# TERMINAL_SHIELD_ESP32.net
KiCad netlist of a schematic drawn in EAGLE
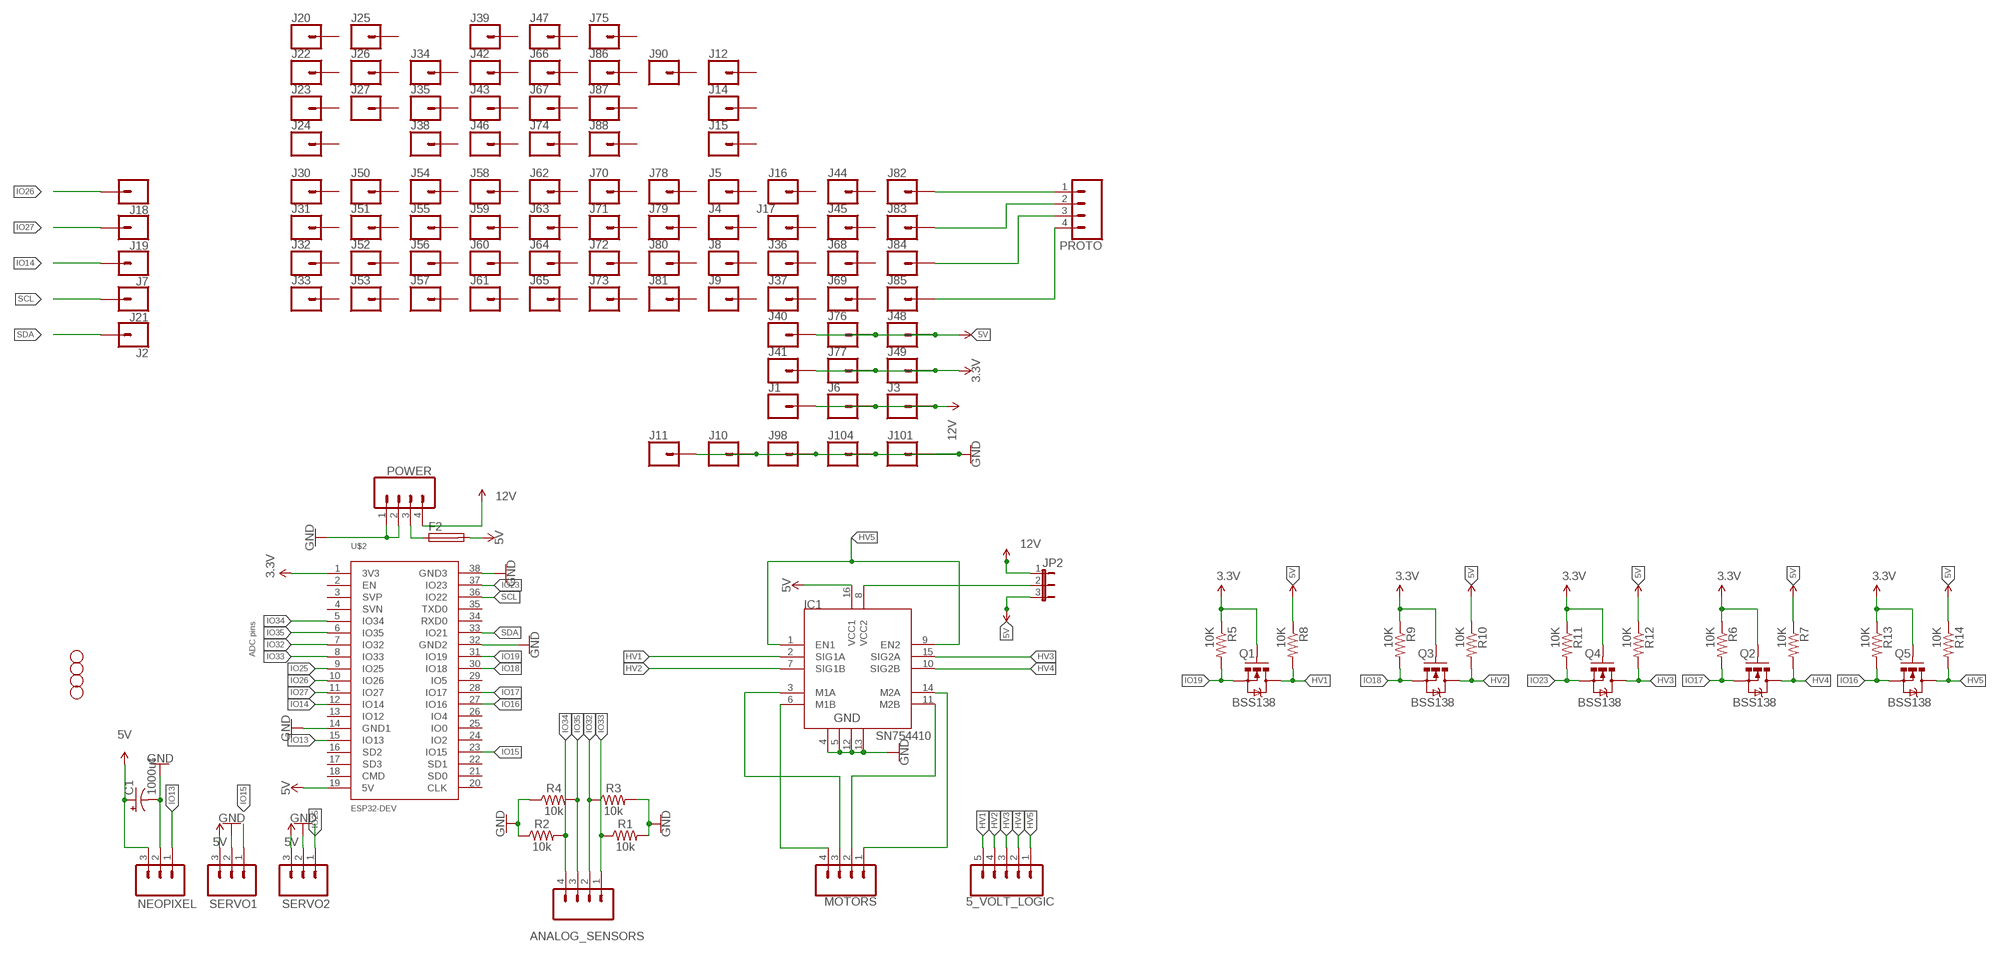
[diagram p0: schematic, sheet 1]

(export (version "E")
  (design (tool "Eeschema 10.0.6"))
  (components
    (comp (ref "5_VOLT_LOGIC")
      (value "CONN_05SCREW")
      (footprint "eagle-import:SCREWTERMINAL-3.5MM-5")
      (libsource (lib "eagle-import") (part "CONN_05SCREW"))
    )
    (comp (ref "ANALOG_SENSORS")
      (value "CONN_04SCREW")
      (footprint "eagle-import:SCREWTERMINAL-3.5MM-4")
      (libsource (lib "eagle-import") (part "CONN_04SCREW"))
    )
    (comp (ref "C1")
      (value "1000uf")
      (footprint "eagle-import:CPOL-RADIAL-5MM-10MM")
      (libsource (lib "eagle-import") (part "1000UF-RADIAL-5MM-25V-20%"))
    )
    (comp (ref "F2")
      (value "KS17")
      (footprint "eagle-import:KS17")
      (libsource (lib "eagle-import") (part "KS17"))
    )
    (comp (ref "H1")
      (value "STAND-OFF")
      (footprint "eagle-import:STAND-OFF")
      (libsource (lib "eagle-import") (part "STAND-OFF"))
    )
    (comp (ref "H2")
      (value "STAND-OFF")
      (footprint "eagle-import:STAND-OFF")
      (libsource (lib "eagle-import") (part "STAND-OFF"))
    )
    (comp (ref "H3")
      (value "STAND-OFF")
      (footprint "eagle-import:STAND-OFF")
      (libsource (lib "eagle-import") (part "STAND-OFF"))
    )
    (comp (ref "H4")
      (value "STAND-OFF")
      (footprint "eagle-import:STAND-OFF")
      (libsource (lib "eagle-import") (part "STAND-OFF"))
    )
    (comp (ref "IC1")
      (value "SN754410")
      (footprint "eagle-import:DIP16")
      (fields (field (name "MF") "Texas Instruments"))
      (libsource (lib "eagle-import") (part "SN754410"))
    )
    (comp (ref "J1")
      (value "CONN_01")
      (footprint "eagle-import:1X01")
      (libsource (lib "eagle-import") (part "CONN_01"))
    )
    (comp (ref "J2")
      (value "CONN_01")
      (footprint "eagle-import:1X01")
      (libsource (lib "eagle-import") (part "CONN_01"))
    )
    (comp (ref "J3")
      (value "CONN_01")
      (footprint "eagle-import:1X01")
      (libsource (lib "eagle-import") (part "CONN_01"))
    )
    (comp (ref "J4")
      (value "CONN_01")
      (footprint "eagle-import:1X01")
      (libsource (lib "eagle-import") (part "CONN_01"))
    )
    (comp (ref "J5")
      (value "CONN_01")
      (footprint "eagle-import:1X01")
      (libsource (lib "eagle-import") (part "CONN_01"))
    )
    (comp (ref "J6")
      (value "CONN_01")
      (footprint "eagle-import:1X01")
      (libsource (lib "eagle-import") (part "CONN_01"))
    )
    (comp (ref "J7")
      (value "CONN_01")
      (footprint "eagle-import:1X01")
      (libsource (lib "eagle-import") (part "CONN_01"))
    )
    (comp (ref "J8")
      (value "CONN_01")
      (footprint "eagle-import:1X01")
      (libsource (lib "eagle-import") (part "CONN_01"))
    )
    (comp (ref "J9")
      (value "CONN_01")
      (footprint "eagle-import:1X01")
      (libsource (lib "eagle-import") (part "CONN_01"))
    )
    (comp (ref "J10")
      (value "CONN_01")
      (footprint "eagle-import:1X01")
      (libsource (lib "eagle-import") (part "CONN_01"))
    )
    (comp (ref "J11")
      (value "CONN_01")
      (footprint "eagle-import:1X01")
      (libsource (lib "eagle-import") (part "CONN_01"))
    )
    (comp (ref "J12")
      (value "CONN_01")
      (footprint "eagle-import:1X01")
      (libsource (lib "eagle-import") (part "CONN_01"))
    )
    (comp (ref "J14")
      (value "CONN_01")
      (footprint "eagle-import:1X01")
      (libsource (lib "eagle-import") (part "CONN_01"))
    )
    (comp (ref "J15")
      (value "CONN_01")
      (footprint "eagle-import:1X01")
      (libsource (lib "eagle-import") (part "CONN_01"))
    )
    (comp (ref "J16")
      (value "CONN_01")
      (footprint "eagle-import:1X01")
      (libsource (lib "eagle-import") (part "CONN_01"))
    )
    (comp (ref "J17")
      (value "CONN_01")
      (footprint "eagle-import:1X01")
      (libsource (lib "eagle-import") (part "CONN_01"))
    )
    (comp (ref "J18")
      (value "CONN_01")
      (footprint "eagle-import:1X01")
      (libsource (lib "eagle-import") (part "CONN_01"))
    )
    (comp (ref "J19")
      (value "CONN_01")
      (footprint "eagle-import:1X01")
      (libsource (lib "eagle-import") (part "CONN_01"))
    )
    (comp (ref "J20")
      (value "CONN_01")
      (footprint "eagle-import:1X01")
      (libsource (lib "eagle-import") (part "CONN_01"))
    )
    (comp (ref "J21")
      (value "CONN_01")
      (footprint "eagle-import:1X01")
      (libsource (lib "eagle-import") (part "CONN_01"))
    )
    (comp (ref "J22")
      (value "CONN_01")
      (footprint "eagle-import:1X01")
      (libsource (lib "eagle-import") (part "CONN_01"))
    )
    (comp (ref "J23")
      (value "CONN_01")
      (footprint "eagle-import:1X01")
      (libsource (lib "eagle-import") (part "CONN_01"))
    )
    (comp (ref "J24")
      (value "CONN_01")
      (footprint "eagle-import:1X01")
      (libsource (lib "eagle-import") (part "CONN_01"))
    )
    (comp (ref "J25")
      (value "CONN_01")
      (footprint "eagle-import:1X01")
      (libsource (lib "eagle-import") (part "CONN_01"))
    )
    (comp (ref "J26")
      (value "CONN_01")
      (footprint "eagle-import:1X01")
      (libsource (lib "eagle-import") (part "CONN_01"))
    )
    (comp (ref "J27")
      (value "CONN_01")
      (footprint "eagle-import:1X01")
      (libsource (lib "eagle-import") (part "CONN_01"))
    )
    (comp (ref "J30")
      (value "CONN_01")
      (footprint "eagle-import:1X01")
      (libsource (lib "eagle-import") (part "CONN_01"))
    )
    (comp (ref "J31")
      (value "CONN_01")
      (footprint "eagle-import:1X01")
      (libsource (lib "eagle-import") (part "CONN_01"))
    )
    (comp (ref "J32")
      (value "CONN_01")
      (footprint "eagle-import:1X01")
      (libsource (lib "eagle-import") (part "CONN_01"))
    )
    (comp (ref "J33")
      (value "CONN_01")
      (footprint "eagle-import:1X01")
      (libsource (lib "eagle-import") (part "CONN_01"))
    )
    (comp (ref "J34")
      (value "CONN_01")
      (footprint "eagle-import:1X01")
      (libsource (lib "eagle-import") (part "CONN_01"))
    )
    (comp (ref "J35")
      (value "CONN_01")
      (footprint "eagle-import:1X01")
      (libsource (lib "eagle-import") (part "CONN_01"))
    )
    (comp (ref "J36")
      (value "CONN_01")
      (footprint "eagle-import:1X01")
      (libsource (lib "eagle-import") (part "CONN_01"))
    )
    (comp (ref "J37")
      (value "CONN_01")
      (footprint "eagle-import:1X01")
      (libsource (lib "eagle-import") (part "CONN_01"))
    )
    (comp (ref "J38")
      (value "CONN_01")
      (footprint "eagle-import:1X01")
      (libsource (lib "eagle-import") (part "CONN_01"))
    )
    (comp (ref "J39")
      (value "CONN_01")
      (footprint "eagle-import:1X01")
      (libsource (lib "eagle-import") (part "CONN_01"))
    )
    (comp (ref "J40")
      (value "CONN_01")
      (footprint "eagle-import:1X01")
      (libsource (lib "eagle-import") (part "CONN_01"))
    )
    (comp (ref "J41")
      (value "CONN_01")
      (footprint "eagle-import:1X01")
      (libsource (lib "eagle-import") (part "CONN_01"))
    )
    (comp (ref "J42")
      (value "CONN_01")
      (footprint "eagle-import:1X01")
      (libsource (lib "eagle-import") (part "CONN_01"))
    )
    (comp (ref "J43")
      (value "CONN_01")
      (footprint "eagle-import:1X01")
      (libsource (lib "eagle-import") (part "CONN_01"))
    )
    (comp (ref "J44")
      (value "CONN_01")
      (footprint "eagle-import:1X01")
      (libsource (lib "eagle-import") (part "CONN_01"))
    )
    (comp (ref "J45")
      (value "CONN_01")
      (footprint "eagle-import:1X01")
      (libsource (lib "eagle-import") (part "CONN_01"))
    )
    (comp (ref "J46")
      (value "CONN_01")
      (footprint "eagle-import:1X01")
      (libsource (lib "eagle-import") (part "CONN_01"))
    )
    (comp (ref "J47")
      (value "CONN_01")
      (footprint "eagle-import:1X01")
      (libsource (lib "eagle-import") (part "CONN_01"))
    )
    (comp (ref "J48")
      (value "CONN_01")
      (footprint "eagle-import:1X01")
      (libsource (lib "eagle-import") (part "CONN_01"))
    )
    (comp (ref "J49")
      (value "CONN_01")
      (footprint "eagle-import:1X01")
      (libsource (lib "eagle-import") (part "CONN_01"))
    )
    (comp (ref "J50")
      (value "CONN_01")
      (footprint "eagle-import:1X01")
      (libsource (lib "eagle-import") (part "CONN_01"))
    )
    (comp (ref "J51")
      (value "CONN_01")
      (footprint "eagle-import:1X01")
      (libsource (lib "eagle-import") (part "CONN_01"))
    )
    (comp (ref "J52")
      (value "CONN_01")
      (footprint "eagle-import:1X01")
      (libsource (lib "eagle-import") (part "CONN_01"))
    )
    (comp (ref "J53")
      (value "CONN_01")
      (footprint "eagle-import:1X01")
      (libsource (lib "eagle-import") (part "CONN_01"))
    )
    (comp (ref "J54")
      (value "CONN_01")
      (footprint "eagle-import:1X01")
      (libsource (lib "eagle-import") (part "CONN_01"))
    )
    (comp (ref "J55")
      (value "CONN_01")
      (footprint "eagle-import:1X01")
      (libsource (lib "eagle-import") (part "CONN_01"))
    )
    (comp (ref "J56")
      (value "CONN_01")
      (footprint "eagle-import:1X01")
      (libsource (lib "eagle-import") (part "CONN_01"))
    )
    (comp (ref "J57")
      (value "CONN_01")
      (footprint "eagle-import:1X01")
      (libsource (lib "eagle-import") (part "CONN_01"))
    )
    (comp (ref "J58")
      (value "CONN_01")
      (footprint "eagle-import:1X01")
      (libsource (lib "eagle-import") (part "CONN_01"))
    )
    (comp (ref "J59")
      (value "CONN_01")
      (footprint "eagle-import:1X01")
      (libsource (lib "eagle-import") (part "CONN_01"))
    )
    (comp (ref "J60")
      (value "CONN_01")
      (footprint "eagle-import:1X01")
      (libsource (lib "eagle-import") (part "CONN_01"))
    )
    (comp (ref "J61")
      (value "CONN_01")
      (footprint "eagle-import:1X01")
      (libsource (lib "eagle-import") (part "CONN_01"))
    )
    (comp (ref "J62")
      (value "CONN_01")
      (footprint "eagle-import:1X01")
      (libsource (lib "eagle-import") (part "CONN_01"))
    )
    (comp (ref "J63")
      (value "CONN_01")
      (footprint "eagle-import:1X01")
      (libsource (lib "eagle-import") (part "CONN_01"))
    )
    (comp (ref "J64")
      (value "CONN_01")
      (footprint "eagle-import:1X01")
      (libsource (lib "eagle-import") (part "CONN_01"))
    )
    (comp (ref "J65")
      (value "CONN_01")
      (footprint "eagle-import:1X01")
      (libsource (lib "eagle-import") (part "CONN_01"))
    )
    (comp (ref "J66")
      (value "CONN_01")
      (footprint "eagle-import:1X01")
      (libsource (lib "eagle-import") (part "CONN_01"))
    )
    (comp (ref "J67")
      (value "CONN_01")
      (footprint "eagle-import:1X01")
      (libsource (lib "eagle-import") (part "CONN_01"))
    )
    (comp (ref "J68")
      (value "CONN_01")
      (footprint "eagle-import:1X01")
      (libsource (lib "eagle-import") (part "CONN_01"))
    )
    (comp (ref "J69")
      (value "CONN_01")
      (footprint "eagle-import:1X01")
      (libsource (lib "eagle-import") (part "CONN_01"))
    )
    (comp (ref "J70")
      (value "CONN_01")
      (footprint "eagle-import:1X01")
      (libsource (lib "eagle-import") (part "CONN_01"))
    )
    (comp (ref "J71")
      (value "CONN_01")
      (footprint "eagle-import:1X01")
      (libsource (lib "eagle-import") (part "CONN_01"))
    )
    (comp (ref "J72")
      (value "CONN_01")
      (footprint "eagle-import:1X01")
      (libsource (lib "eagle-import") (part "CONN_01"))
    )
    (comp (ref "J73")
      (value "CONN_01")
      (footprint "eagle-import:1X01")
      (libsource (lib "eagle-import") (part "CONN_01"))
    )
    (comp (ref "J74")
      (value "CONN_01")
      (footprint "eagle-import:1X01")
      (libsource (lib "eagle-import") (part "CONN_01"))
    )
    (comp (ref "J75")
      (value "CONN_01")
      (footprint "eagle-import:1X01")
      (libsource (lib "eagle-import") (part "CONN_01"))
    )
    (comp (ref "J76")
      (value "CONN_01")
      (footprint "eagle-import:1X01")
      (libsource (lib "eagle-import") (part "CONN_01"))
    )
    (comp (ref "J77")
      (value "CONN_01")
      (footprint "eagle-import:1X01")
      (libsource (lib "eagle-import") (part "CONN_01"))
    )
    (comp (ref "J78")
      (value "CONN_01")
      (footprint "eagle-import:1X01")
      (libsource (lib "eagle-import") (part "CONN_01"))
    )
    (comp (ref "J79")
      (value "CONN_01")
      (footprint "eagle-import:1X01")
      (libsource (lib "eagle-import") (part "CONN_01"))
    )
    (comp (ref "J80")
      (value "CONN_01")
      (footprint "eagle-import:1X01")
      (libsource (lib "eagle-import") (part "CONN_01"))
    )
    (comp (ref "J81")
      (value "CONN_01")
      (footprint "eagle-import:1X01")
      (libsource (lib "eagle-import") (part "CONN_01"))
    )
    (comp (ref "J82")
      (value "CONN_01")
      (footprint "eagle-import:1X01")
      (libsource (lib "eagle-import") (part "CONN_01"))
    )
    (comp (ref "J83")
      (value "CONN_01")
      (footprint "eagle-import:1X01")
      (libsource (lib "eagle-import") (part "CONN_01"))
    )
    (comp (ref "J84")
      (value "CONN_01")
      (footprint "eagle-import:1X01")
      (libsource (lib "eagle-import") (part "CONN_01"))
    )
    (comp (ref "J85")
      (value "CONN_01")
      (footprint "eagle-import:1X01")
      (libsource (lib "eagle-import") (part "CONN_01"))
    )
    (comp (ref "J86")
      (value "CONN_01")
      (footprint "eagle-import:1X01")
      (libsource (lib "eagle-import") (part "CONN_01"))
    )
    (comp (ref "J87")
      (value "CONN_01")
      (footprint "eagle-import:1X01")
      (libsource (lib "eagle-import") (part "CONN_01"))
    )
    (comp (ref "J88")
      (value "CONN_01")
      (footprint "eagle-import:1X01")
      (libsource (lib "eagle-import") (part "CONN_01"))
    )
    (comp (ref "J90")
      (value "CONN_01")
      (footprint "eagle-import:1X01")
      (libsource (lib "eagle-import") (part "CONN_01"))
    )
    (comp (ref "J98")
      (value "CONN_01")
      (footprint "eagle-import:1X01")
      (libsource (lib "eagle-import") (part "CONN_01"))
    )
    (comp (ref "J101")
      (value "CONN_01")
      (footprint "eagle-import:1X01")
      (libsource (lib "eagle-import") (part "CONN_01"))
    )
    (comp (ref "J104")
      (value "CONN_01")
      (footprint "eagle-import:1X01")
      (libsource (lib "eagle-import") (part "CONN_01"))
    )
    (comp (ref "JP2")
      (value "JP2E")
      (footprint "eagle-import:JP2")
      (libsource (lib "eagle-import") (part "JP2E"))
    )
    (comp (ref "MOTORS")
      (value "CONN_04SCREW")
      (footprint "eagle-import:SCREWTERMINAL-3.5MM-4")
      (libsource (lib "eagle-import") (part "CONN_04SCREW"))
    )
    (comp (ref "NEOPIXEL")
      (value "CONN_03SCREW")
      (footprint "eagle-import:SCREWTERMINAL-3.5MM-3")
      (libsource (lib "eagle-import") (part "CONN_03SCREW"))
    )
    (comp (ref "POWER")
      (value "CONN_04SCREW")
      (footprint "eagle-import:SCREWTERMINAL-3.5MM-4")
      (libsource (lib "eagle-import") (part "CONN_04SCREW"))
    )
    (comp (ref "PROTO")
      (value "CONN_04SCREW")
      (footprint "eagle-import:SCREWTERMINAL-3.5MM-4")
      (libsource (lib "eagle-import") (part "CONN_04SCREW"))
    )
    (comp (ref "Q1")
      (value "BSS138")
      (footprint "eagle-import:SOT23-3")
      (libsource (lib "eagle-import") (part "MOSFET-NCHANNELSMD"))
    )
    (comp (ref "Q2")
      (value "BSS138")
      (footprint "eagle-import:SOT23-3")
      (libsource (lib "eagle-import") (part "MOSFET-NCHANNELSMD"))
    )
    (comp (ref "Q3")
      (value "BSS138")
      (footprint "eagle-import:SOT23-3")
      (libsource (lib "eagle-import") (part "MOSFET-NCHANNELSMD"))
    )
    (comp (ref "Q4")
      (value "BSS138")
      (footprint "eagle-import:SOT23-3")
      (libsource (lib "eagle-import") (part "MOSFET-NCHANNELSMD"))
    )
    (comp (ref "Q5")
      (value "BSS138")
      (footprint "eagle-import:SOT23-3")
      (libsource (lib "eagle-import") (part "MOSFET-NCHANNELSMD"))
    )
    (comp (ref "R1")
      (value "10k")
      (footprint "eagle-import:AXIAL-0.3")
      (libsource (lib "eagle-import") (part "10KOHM-HORIZ-1/4W-1%"))
    )
    (comp (ref "R2")
      (value "10k")
      (footprint "eagle-import:AXIAL-0.3")
      (libsource (lib "eagle-import") (part "10KOHM-HORIZ-1/4W-1%"))
    )
    (comp (ref "R3")
      (value "10k")
      (footprint "eagle-import:AXIAL-0.3")
      (libsource (lib "eagle-import") (part "10KOHM-HORIZ-1/4W-1%"))
    )
    (comp (ref "R4")
      (value "10k")
      (footprint "eagle-import:AXIAL-0.3")
      (libsource (lib "eagle-import") (part "10KOHM-HORIZ-1/4W-1%"))
    )
    (comp (ref "R5")
      (value "10K")
      (footprint "eagle-import:0805")
      (libsource (lib "eagle-import") (part "RESISTOR0805-RES"))
    )
    (comp (ref "R6")
      (value "10K")
      (footprint "eagle-import:0805")
      (libsource (lib "eagle-import") (part "RESISTOR0805-RES"))
    )
    (comp (ref "R7")
      (value "10K")
      (footprint "eagle-import:0805")
      (libsource (lib "eagle-import") (part "RESISTOR0805-RES"))
    )
    (comp (ref "R8")
      (value "10K")
      (footprint "eagle-import:0805")
      (libsource (lib "eagle-import") (part "RESISTOR0805-RES"))
    )
    (comp (ref "R9")
      (value "10K")
      (footprint "eagle-import:0805")
      (libsource (lib "eagle-import") (part "RESISTOR0805-RES"))
    )
    (comp (ref "R10")
      (value "10K")
      (footprint "eagle-import:0805")
      (libsource (lib "eagle-import") (part "RESISTOR0805-RES"))
    )
    (comp (ref "R11")
      (value "10K")
      (footprint "eagle-import:0805")
      (libsource (lib "eagle-import") (part "RESISTOR0805-RES"))
    )
    (comp (ref "R12")
      (value "10K")
      (footprint "eagle-import:0805")
      (libsource (lib "eagle-import") (part "RESISTOR0805-RES"))
    )
    (comp (ref "R13")
      (value "10K")
      (footprint "eagle-import:0805")
      (libsource (lib "eagle-import") (part "RESISTOR0805-RES"))
    )
    (comp (ref "R14")
      (value "10K")
      (footprint "eagle-import:0805")
      (libsource (lib "eagle-import") (part "RESISTOR0805-RES"))
    )
    (comp (ref "SERVO1")
      (value "CONN_03SCREW")
      (footprint "eagle-import:SCREWTERMINAL-3.5MM-3")
      (libsource (lib "eagle-import") (part "CONN_03SCREW"))
    )
    (comp (ref "SERVO2")
      (value "CONN_03SCREW")
      (footprint "eagle-import:SCREWTERMINAL-3.5MM-3")
      (libsource (lib "eagle-import") (part "CONN_03SCREW"))
    )
    (comp (ref "U$2")
      (value "ESP32-DEV")
      (footprint "eagle-import:ESP32-DEV")
      (libsource (lib "eagle-import") (part "ESP32-DEV"))
    )
  )
  (nets
    (net (code "1") (name "3.3V") (class "Default")
      (node (ref "J41") (pin "1") (pinfunction "1_1") (pintype "passive"))
      (node (ref "J49") (pin "1") (pinfunction "1_1") (pintype "passive"))
      (node (ref "J77") (pin "1") (pinfunction "1_1") (pintype "passive"))
      (node (ref "Q1") (pin "1") (pinfunction "G_1") (pintype "passive"))
      (node (ref "Q2") (pin "1") (pinfunction "G_1") (pintype "passive"))
      (node (ref "Q3") (pin "1") (pinfunction "G_1") (pintype "passive"))
      (node (ref "Q4") (pin "1") (pinfunction "G_1") (pintype "passive"))
      (node (ref "Q5") (pin "1") (pinfunction "G_1") (pintype "passive"))
      (node (ref "R11") (pin "1") (pinfunction "1_1") (pintype "passive"))
      (node (ref "R13") (pin "1") (pinfunction "1_1") (pintype "passive"))
      (node (ref "R5") (pin "1") (pinfunction "1_1") (pintype "passive"))
      (node (ref "R6") (pin "1") (pinfunction "1_1") (pintype "passive"))
      (node (ref "R9") (pin "1") (pinfunction "1_1") (pintype "passive"))
      (node (ref "U$2") (pin "1") (pinfunction "3V3_1") (pintype "bidirectional"))
    )
    (net (code "2") (name "5V") (class "Default")
      (node (ref "C1") (pin "+") (pinfunction "+_+") (pintype "passive"))
      (node (ref "F2") (pin "2") (pinfunction "2_2") (pintype "passive"))
      (node (ref "IC1") (pin "16") (pinfunction "VCC1_16") (pintype "power_in"))
      (node (ref "J40") (pin "1") (pinfunction "1_1") (pintype "passive"))
      (node (ref "J48") (pin "1") (pinfunction "1_1") (pintype "passive"))
      (node (ref "J76") (pin "1") (pinfunction "1_1") (pintype "passive"))
      (node (ref "JP2") (pin "3") (pinfunction "3_3") (pintype "passive"))
      (node (ref "NEOPIXEL") (pin "3") (pinfunction "3_3") (pintype "passive"))
      (node (ref "R10") (pin "1") (pinfunction "1_1") (pintype "passive"))
      (node (ref "R12") (pin "1") (pinfunction "1_1") (pintype "passive"))
      (node (ref "R14") (pin "1") (pinfunction "1_1") (pintype "passive"))
      (node (ref "R7") (pin "1") (pinfunction "1_1") (pintype "passive"))
      (node (ref "R8") (pin "1") (pinfunction "1_1") (pintype "passive"))
      (node (ref "SERVO1") (pin "3") (pinfunction "3_3") (pintype "passive"))
      (node (ref "SERVO2") (pin "3") (pinfunction "3_3") (pintype "passive"))
      (node (ref "U$2") (pin "19") (pinfunction "5V_19") (pintype "bidirectional"))
    )
    (net (code "3") (name "12V") (class "Default")
      (node (ref "J1") (pin "1") (pinfunction "1_1") (pintype "passive"))
      (node (ref "J3") (pin "1") (pinfunction "1_1") (pintype "passive"))
      (node (ref "J6") (pin "1") (pinfunction "1_1") (pintype "passive"))
      (node (ref "JP2") (pin "1") (pinfunction "1_1") (pintype "passive"))
      (node (ref "POWER") (pin "4") (pinfunction "4_4") (pintype "passive"))
    )
    (net (code "4") (name "GND") (class "Default")
      (node (ref "C1") (pin "-") (pinfunction "-_-") (pintype "passive"))
      (node (ref "IC1") (pin "12") (pinfunction "P12_12") (pintype "power_in"))
      (node (ref "IC1") (pin "13") (pinfunction "P13_13") (pintype "power_in"))
      (node (ref "IC1") (pin "4") (pinfunction "P4_4") (pintype "power_in"))
      (node (ref "IC1") (pin "5") (pinfunction "P5_5") (pintype "power_in"))
      (node (ref "J10") (pin "1") (pinfunction "1_1") (pintype "passive"))
      (node (ref "J101") (pin "1") (pinfunction "1_1") (pintype "passive"))
      (node (ref "J104") (pin "1") (pinfunction "1_1") (pintype "passive"))
      (node (ref "J11") (pin "1") (pinfunction "1_1") (pintype "passive"))
      (node (ref "J98") (pin "1") (pinfunction "1_1") (pintype "passive"))
      (node (ref "NEOPIXEL") (pin "2") (pinfunction "2_2") (pintype "passive"))
      (node (ref "POWER") (pin "1") (pinfunction "1_1") (pintype "passive"))
      (node (ref "POWER") (pin "2") (pinfunction "2_2") (pintype "passive"))
      (node (ref "R1") (pin "P$2") (pinfunction "2_P$2") (pintype "passive"))
      (node (ref "R2") (pin "P$1") (pinfunction "1_P$1") (pintype "passive"))
      (node (ref "R3") (pin "P$2") (pinfunction "2_P$2") (pintype "passive"))
      (node (ref "R4") (pin "P$1") (pinfunction "1_P$1") (pintype "passive"))
      (node (ref "SERVO1") (pin "2") (pinfunction "2_2") (pintype "passive"))
      (node (ref "SERVO2") (pin "2") (pinfunction "2_2") (pintype "passive"))
      (node (ref "U$2") (pin "14") (pinfunction "GND1_14") (pintype "bidirectional"))
      (node (ref "U$2") (pin "32") (pinfunction "GND2_32") (pintype "bidirectional"))
      (node (ref "U$2") (pin "38") (pinfunction "GND3_38") (pintype "bidirectional"))
    )
    (net (code "5") (name "HV1") (class "Default")
      (node (ref "5_VOLT_LOGIC") (pin "5") (pinfunction "5_5") (pintype "passive"))
      (node (ref "IC1") (pin "2") (pinfunction "SIG1A_2") (pintype "bidirectional"))
      (node (ref "Q1") (pin "3") (pinfunction "D_3") (pintype "passive"))
      (node (ref "R8") (pin "2") (pinfunction "2_2") (pintype "passive"))
    )
    (net (code "6") (name "HV2") (class "Default")
      (node (ref "5_VOLT_LOGIC") (pin "4") (pinfunction "4_4") (pintype "passive"))
      (node (ref "IC1") (pin "7") (pinfunction "SIG1B_7") (pintype "bidirectional"))
      (node (ref "Q3") (pin "3") (pinfunction "D_3") (pintype "passive"))
      (node (ref "R10") (pin "2") (pinfunction "2_2") (pintype "passive"))
    )
    (net (code "7") (name "HV3") (class "Default")
      (node (ref "5_VOLT_LOGIC") (pin "3") (pinfunction "3_3") (pintype "passive"))
      (node (ref "IC1") (pin "15") (pinfunction "SIG2A_15") (pintype "bidirectional"))
      (node (ref "Q4") (pin "3") (pinfunction "D_3") (pintype "passive"))
      (node (ref "R12") (pin "2") (pinfunction "2_2") (pintype "passive"))
    )
    (net (code "8") (name "HV4") (class "Default")
      (node (ref "5_VOLT_LOGIC") (pin "2") (pinfunction "2_2") (pintype "passive"))
      (node (ref "IC1") (pin "10") (pinfunction "SIG2B_10") (pintype "bidirectional"))
      (node (ref "Q2") (pin "3") (pinfunction "D_3") (pintype "passive"))
      (node (ref "R7") (pin "2") (pinfunction "2_2") (pintype "passive"))
    )
    (net (code "9") (name "HV5") (class "Default")
      (node (ref "5_VOLT_LOGIC") (pin "1") (pinfunction "1_1") (pintype "passive"))
      (node (ref "IC1") (pin "1") (pinfunction "EN1_1") (pintype "bidirectional"))
      (node (ref "IC1") (pin "9") (pinfunction "EN2_9") (pintype "bidirectional"))
      (node (ref "Q5") (pin "3") (pinfunction "D_3") (pintype "passive"))
      (node (ref "R14") (pin "2") (pinfunction "2_2") (pintype "passive"))
    )
    (net (code "10") (name "IO13") (class "Default")
      (node (ref "NEOPIXEL") (pin "1") (pinfunction "1_1") (pintype "passive"))
      (node (ref "U$2") (pin "15") (pinfunction "IO13_15") (pintype "bidirectional"))
    )
    (net (code "11") (name "IO14") (class "Default")
      (node (ref "J7") (pin "1") (pinfunction "1_1") (pintype "passive"))
      (node (ref "U$2") (pin "12") (pinfunction "IO14_12") (pintype "bidirectional"))
    )
    (net (code "12") (name "IO15") (class "Default")
      (node (ref "SERVO1") (pin "1") (pinfunction "1_1") (pintype "passive"))
      (node (ref "U$2") (pin "23") (pinfunction "IO15_23") (pintype "bidirectional"))
    )
    (net (code "13") (name "IO16") (class "Default")
      (node (ref "Q5") (pin "2") (pinfunction "S_2") (pintype "passive"))
      (node (ref "R13") (pin "2") (pinfunction "2_2") (pintype "passive"))
      (node (ref "U$2") (pin "27") (pinfunction "IO16_27") (pintype "bidirectional"))
    )
    (net (code "14") (name "IO17") (class "Default")
      (node (ref "Q2") (pin "2") (pinfunction "S_2") (pintype "passive"))
      (node (ref "R6") (pin "2") (pinfunction "2_2") (pintype "passive"))
      (node (ref "U$2") (pin "28") (pinfunction "IO17_28") (pintype "bidirectional"))
    )
    (net (code "15") (name "IO18") (class "Default")
      (node (ref "Q3") (pin "2") (pinfunction "S_2") (pintype "passive"))
      (node (ref "R9") (pin "2") (pinfunction "2_2") (pintype "passive"))
      (node (ref "U$2") (pin "30") (pinfunction "IO18_30") (pintype "bidirectional"))
    )
    (net (code "16") (name "IO19") (class "Default")
      (node (ref "Q1") (pin "2") (pinfunction "S_2") (pintype "passive"))
      (node (ref "R5") (pin "2") (pinfunction "2_2") (pintype "passive"))
      (node (ref "U$2") (pin "31") (pinfunction "IO19_31") (pintype "bidirectional"))
    )
    (net (code "17") (name "IO23") (class "Default")
      (node (ref "Q4") (pin "2") (pinfunction "S_2") (pintype "passive"))
      (node (ref "R11") (pin "2") (pinfunction "2_2") (pintype "passive"))
      (node (ref "U$2") (pin "37") (pinfunction "IO23_37") (pintype "bidirectional"))
    )
    (net (code "18") (name "IO25") (class "Default")
      (node (ref "SERVO2") (pin "1") (pinfunction "1_1") (pintype "passive"))
      (node (ref "U$2") (pin "9") (pinfunction "IO25_9") (pintype "bidirectional"))
    )
    (net (code "19") (name "IO26") (class "Default")
      (node (ref "J18") (pin "1") (pinfunction "1_1") (pintype "passive"))
      (node (ref "U$2") (pin "10") (pinfunction "IO26_10") (pintype "bidirectional"))
    )
    (net (code "20") (name "IO27") (class "Default")
      (node (ref "J19") (pin "1") (pinfunction "1_1") (pintype "passive"))
      (node (ref "U$2") (pin "11") (pinfunction "IO27_11") (pintype "bidirectional"))
    )
    (net (code "21") (name "IO32") (class "Default")
      (node (ref "ANALOG_SENSORS") (pin "2") (pinfunction "2_2") (pintype "passive"))
      (node (ref "R3") (pin "P$1") (pinfunction "1_P$1") (pintype "passive"))
      (node (ref "U$2") (pin "7") (pinfunction "IO32_7") (pintype "bidirectional"))
    )
    (net (code "22") (name "IO33") (class "Default")
      (node (ref "ANALOG_SENSORS") (pin "1") (pinfunction "1_1") (pintype "passive"))
      (node (ref "R1") (pin "P$1") (pinfunction "1_P$1") (pintype "passive"))
      (node (ref "U$2") (pin "8") (pinfunction "IO33_8") (pintype "bidirectional"))
    )
    (net (code "23") (name "IO34") (class "Default")
      (node (ref "ANALOG_SENSORS") (pin "4") (pinfunction "4_4") (pintype "passive"))
      (node (ref "R2") (pin "P$2") (pinfunction "2_P$2") (pintype "passive"))
      (node (ref "U$2") (pin "5") (pinfunction "IO34_5") (pintype "bidirectional"))
    )
    (net (code "24") (name "IO35") (class "Default")
      (node (ref "ANALOG_SENSORS") (pin "3") (pinfunction "3_3") (pintype "passive"))
      (node (ref "R4") (pin "P$2") (pinfunction "2_P$2") (pintype "passive"))
      (node (ref "U$2") (pin "6") (pinfunction "IO35_6") (pintype "bidirectional"))
    )
    (net (code "25") (name "Net-(F2-Pad1)") (class "Default")
      (node (ref "F2") (pin "1") (pinfunction "1_1") (pintype "passive"))
      (node (ref "POWER") (pin "3") (pinfunction "3_3") (pintype "passive"))
    )
    (net (code "26") (name "Net-(IC1-M1A)") (class "Default")
      (node (ref "IC1") (pin "3") (pinfunction "M1A_3") (pintype "bidirectional"))
      (node (ref "MOTORS") (pin "3") (pinfunction "3_3") (pintype "passive"))
    )
    (net (code "27") (name "Net-(IC1-M1B)") (class "Default")
      (node (ref "IC1") (pin "6") (pinfunction "M1B_6") (pintype "bidirectional"))
      (node (ref "MOTORS") (pin "4") (pinfunction "4_4") (pintype "passive"))
    )
    (net (code "28") (name "Net-(IC1-M2A)") (class "Default")
      (node (ref "IC1") (pin "14") (pinfunction "M2A_14") (pintype "bidirectional"))
      (node (ref "MOTORS") (pin "1") (pinfunction "1_1") (pintype "passive"))
    )
    (net (code "29") (name "Net-(IC1-M2B)") (class "Default")
      (node (ref "IC1") (pin "11") (pinfunction "M2B_11") (pintype "bidirectional"))
      (node (ref "MOTORS") (pin "2") (pinfunction "2_2") (pintype "passive"))
    )
    (net (code "30") (name "Net-(IC1-VCC2)") (class "Default")
      (node (ref "IC1") (pin "8") (pinfunction "VCC2_8") (pintype "power_in"))
      (node (ref "JP2") (pin "2") (pinfunction "2_2") (pintype "passive"))
    )
    (net (code "31") (name "Net-(J82-Pad1)") (class "Default")
      (node (ref "J82") (pin "1") (pinfunction "1_1") (pintype "passive"))
      (node (ref "PROTO") (pin "1") (pinfunction "1_1") (pintype "passive"))
    )
    (net (code "32") (name "Net-(J83-Pad1)") (class "Default")
      (node (ref "J83") (pin "1") (pinfunction "1_1") (pintype "passive"))
      (node (ref "PROTO") (pin "2") (pinfunction "2_2") (pintype "passive"))
    )
    (net (code "33") (name "Net-(J84-Pad1)") (class "Default")
      (node (ref "J84") (pin "1") (pinfunction "1_1") (pintype "passive"))
      (node (ref "PROTO") (pin "3") (pinfunction "3_3") (pintype "passive"))
    )
    (net (code "34") (name "Net-(J85-Pad1)") (class "Default")
      (node (ref "J85") (pin "1") (pinfunction "1_1") (pintype "passive"))
      (node (ref "PROTO") (pin "4") (pinfunction "4_4") (pintype "passive"))
    )
    (net (code "35") (name "SCL") (class "Default")
      (node (ref "J21") (pin "1") (pinfunction "1_1") (pintype "passive"))
      (node (ref "U$2") (pin "36") (pinfunction "IO22_36") (pintype "bidirectional"))
    )
    (net (code "36") (name "SDA") (class "Default")
      (node (ref "J2") (pin "1") (pinfunction "1_1") (pintype "passive"))
      (node (ref "U$2") (pin "33") (pinfunction "IO21_33") (pintype "bidirectional"))
    )
    (net (code "37") (name "unconnected-(J4-Pad1)") (class "Default")
      (node (ref "J4") (pin "1") (pinfunction "1_1") (pintype "passive"))
    )
    (net (code "38") (name "unconnected-(J5-Pad1)") (class "Default")
      (node (ref "J5") (pin "1") (pinfunction "1_1") (pintype "passive"))
    )
    (net (code "39") (name "unconnected-(J8-Pad1)") (class "Default")
      (node (ref "J8") (pin "1") (pinfunction "1_1") (pintype "passive"))
    )
    (net (code "40") (name "unconnected-(J9-Pad1)") (class "Default")
      (node (ref "J9") (pin "1") (pinfunction "1_1") (pintype "passive"))
    )
    (net (code "41") (name "unconnected-(J12-Pad1)") (class "Default")
      (node (ref "J12") (pin "1") (pinfunction "1_1") (pintype "passive"))
    )
    (net (code "42") (name "unconnected-(J14-Pad1)") (class "Default")
      (node (ref "J14") (pin "1") (pinfunction "1_1") (pintype "passive"))
    )
    (net (code "43") (name "unconnected-(J15-Pad1)") (class "Default")
      (node (ref "J15") (pin "1") (pinfunction "1_1") (pintype "passive"))
    )
    (net (code "44") (name "unconnected-(J16-Pad1)") (class "Default")
      (node (ref "J16") (pin "1") (pinfunction "1_1") (pintype "passive"))
    )
    (net (code "45") (name "unconnected-(J17-Pad1)") (class "Default")
      (node (ref "J17") (pin "1") (pinfunction "1_1") (pintype "passive"))
    )
    (net (code "46") (name "unconnected-(J20-Pad1)") (class "Default")
      (node (ref "J20") (pin "1") (pinfunction "1_1") (pintype "passive"))
    )
    (net (code "47") (name "unconnected-(J22-Pad1)") (class "Default")
      (node (ref "J22") (pin "1") (pinfunction "1_1") (pintype "passive"))
    )
    (net (code "48") (name "unconnected-(J23-Pad1)") (class "Default")
      (node (ref "J23") (pin "1") (pinfunction "1_1") (pintype "passive"))
    )
    (net (code "49") (name "unconnected-(J24-Pad1)") (class "Default")
      (node (ref "J24") (pin "1") (pinfunction "1_1") (pintype "passive"))
    )
    (net (code "50") (name "unconnected-(J25-Pad1)") (class "Default")
      (node (ref "J25") (pin "1") (pinfunction "1_1") (pintype "passive"))
    )
    (net (code "51") (name "unconnected-(J26-Pad1)") (class "Default")
      (node (ref "J26") (pin "1") (pinfunction "1_1") (pintype "passive"))
    )
    (net (code "52") (name "unconnected-(J27-Pad1)") (class "Default")
      (node (ref "J27") (pin "1") (pinfunction "1_1") (pintype "passive"))
    )
    (net (code "53") (name "unconnected-(J30-Pad1)") (class "Default")
      (node (ref "J30") (pin "1") (pinfunction "1_1") (pintype "passive"))
    )
    (net (code "54") (name "unconnected-(J31-Pad1)") (class "Default")
      (node (ref "J31") (pin "1") (pinfunction "1_1") (pintype "passive"))
    )
    (net (code "55") (name "unconnected-(J32-Pad1)") (class "Default")
      (node (ref "J32") (pin "1") (pinfunction "1_1") (pintype "passive"))
    )
    (net (code "56") (name "unconnected-(J33-Pad1)") (class "Default")
      (node (ref "J33") (pin "1") (pinfunction "1_1") (pintype "passive"))
    )
    (net (code "57") (name "unconnected-(J34-Pad1)") (class "Default")
      (node (ref "J34") (pin "1") (pinfunction "1_1") (pintype "passive"))
    )
    (net (code "58") (name "unconnected-(J35-Pad1)") (class "Default")
      (node (ref "J35") (pin "1") (pinfunction "1_1") (pintype "passive"))
    )
    (net (code "59") (name "unconnected-(J36-Pad1)") (class "Default")
      (node (ref "J36") (pin "1") (pinfunction "1_1") (pintype "passive"))
    )
    (net (code "60") (name "unconnected-(J37-Pad1)") (class "Default")
      (node (ref "J37") (pin "1") (pinfunction "1_1") (pintype "passive"))
    )
    (net (code "61") (name "unconnected-(J38-Pad1)") (class "Default")
      (node (ref "J38") (pin "1") (pinfunction "1_1") (pintype "passive"))
    )
    (net (code "62") (name "unconnected-(J39-Pad1)") (class "Default")
      (node (ref "J39") (pin "1") (pinfunction "1_1") (pintype "passive"))
    )
    (net (code "63") (name "unconnected-(J42-Pad1)") (class "Default")
      (node (ref "J42") (pin "1") (pinfunction "1_1") (pintype "passive"))
    )
    (net (code "64") (name "unconnected-(J43-Pad1)") (class "Default")
      (node (ref "J43") (pin "1") (pinfunction "1_1") (pintype "passive"))
    )
    (net (code "65") (name "unconnected-(J44-Pad1)") (class "Default")
      (node (ref "J44") (pin "1") (pinfunction "1_1") (pintype "passive"))
    )
    (net (code "66") (name "unconnected-(J45-Pad1)") (class "Default")
      (node (ref "J45") (pin "1") (pinfunction "1_1") (pintype "passive"))
    )
    (net (code "67") (name "unconnected-(J46-Pad1)") (class "Default")
      (node (ref "J46") (pin "1") (pinfunction "1_1") (pintype "passive"))
    )
    (net (code "68") (name "unconnected-(J47-Pad1)") (class "Default")
      (node (ref "J47") (pin "1") (pinfunction "1_1") (pintype "passive"))
    )
    (net (code "69") (name "unconnected-(J50-Pad1)") (class "Default")
      (node (ref "J50") (pin "1") (pinfunction "1_1") (pintype "passive"))
    )
    (net (code "70") (name "unconnected-(J51-Pad1)") (class "Default")
      (node (ref "J51") (pin "1") (pinfunction "1_1") (pintype "passive"))
    )
    (net (code "71") (name "unconnected-(J52-Pad1)") (class "Default")
      (node (ref "J52") (pin "1") (pinfunction "1_1") (pintype "passive"))
    )
    (net (code "72") (name "unconnected-(J53-Pad1)") (class "Default")
      (node (ref "J53") (pin "1") (pinfunction "1_1") (pintype "passive"))
    )
    (net (code "73") (name "unconnected-(J54-Pad1)") (class "Default")
      (node (ref "J54") (pin "1") (pinfunction "1_1") (pintype "passive"))
    )
    (net (code "74") (name "unconnected-(J55-Pad1)") (class "Default")
      (node (ref "J55") (pin "1") (pinfunction "1_1") (pintype "passive"))
    )
    (net (code "75") (name "unconnected-(J56-Pad1)") (class "Default")
      (node (ref "J56") (pin "1") (pinfunction "1_1") (pintype "passive"))
    )
    (net (code "76") (name "unconnected-(J57-Pad1)") (class "Default")
      (node (ref "J57") (pin "1") (pinfunction "1_1") (pintype "passive"))
    )
    (net (code "77") (name "unconnected-(J58-Pad1)") (class "Default")
      (node (ref "J58") (pin "1") (pinfunction "1_1") (pintype "passive"))
    )
    (net (code "78") (name "unconnected-(J59-Pad1)") (class "Default")
      (node (ref "J59") (pin "1") (pinfunction "1_1") (pintype "passive"))
    )
    (net (code "79") (name "unconnected-(J60-Pad1)") (class "Default")
      (node (ref "J60") (pin "1") (pinfunction "1_1") (pintype "passive"))
    )
    (net (code "80") (name "unconnected-(J61-Pad1)") (class "Default")
      (node (ref "J61") (pin "1") (pinfunction "1_1") (pintype "passive"))
    )
    (net (code "81") (name "unconnected-(J62-Pad1)") (class "Default")
      (node (ref "J62") (pin "1") (pinfunction "1_1") (pintype "passive"))
    )
    (net (code "82") (name "unconnected-(J63-Pad1)") (class "Default")
      (node (ref "J63") (pin "1") (pinfunction "1_1") (pintype "passive"))
    )
    (net (code "83") (name "unconnected-(J64-Pad1)") (class "Default")
      (node (ref "J64") (pin "1") (pinfunction "1_1") (pintype "passive"))
    )
    (net (code "84") (name "unconnected-(J65-Pad1)") (class "Default")
      (node (ref "J65") (pin "1") (pinfunction "1_1") (pintype "passive"))
    )
    (net (code "85") (name "unconnected-(J66-Pad1)") (class "Default")
      (node (ref "J66") (pin "1") (pinfunction "1_1") (pintype "passive"))
    )
    (net (code "86") (name "unconnected-(J67-Pad1)") (class "Default")
      (node (ref "J67") (pin "1") (pinfunction "1_1") (pintype "passive"))
    )
    (net (code "87") (name "unconnected-(J68-Pad1)") (class "Default")
      (node (ref "J68") (pin "1") (pinfunction "1_1") (pintype "passive"))
    )
    (net (code "88") (name "unconnected-(J69-Pad1)") (class "Default")
      (node (ref "J69") (pin "1") (pinfunction "1_1") (pintype "passive"))
    )
    (net (code "89") (name "unconnected-(J70-Pad1)") (class "Default")
      (node (ref "J70") (pin "1") (pinfunction "1_1") (pintype "passive"))
    )
    (net (code "90") (name "unconnected-(J71-Pad1)") (class "Default")
      (node (ref "J71") (pin "1") (pinfunction "1_1") (pintype "passive"))
    )
    (net (code "91") (name "unconnected-(J72-Pad1)") (class "Default")
      (node (ref "J72") (pin "1") (pinfunction "1_1") (pintype "passive"))
    )
    (net (code "92") (name "unconnected-(J73-Pad1)") (class "Default")
      (node (ref "J73") (pin "1") (pinfunction "1_1") (pintype "passive"))
    )
    (net (code "93") (name "unconnected-(J74-Pad1)") (class "Default")
      (node (ref "J74") (pin "1") (pinfunction "1_1") (pintype "passive"))
    )
    (net (code "94") (name "unconnected-(J75-Pad1)") (class "Default")
      (node (ref "J75") (pin "1") (pinfunction "1_1") (pintype "passive"))
    )
    (net (code "95") (name "unconnected-(J78-Pad1)") (class "Default")
      (node (ref "J78") (pin "1") (pinfunction "1_1") (pintype "passive"))
    )
    (net (code "96") (name "unconnected-(J79-Pad1)") (class "Default")
      (node (ref "J79") (pin "1") (pinfunction "1_1") (pintype "passive"))
    )
    (net (code "97") (name "unconnected-(J80-Pad1)") (class "Default")
      (node (ref "J80") (pin "1") (pinfunction "1_1") (pintype "passive"))
    )
    (net (code "98") (name "unconnected-(J81-Pad1)") (class "Default")
      (node (ref "J81") (pin "1") (pinfunction "1_1") (pintype "passive"))
    )
    (net (code "99") (name "unconnected-(J86-Pad1)") (class "Default")
      (node (ref "J86") (pin "1") (pinfunction "1_1") (pintype "passive"))
    )
    (net (code "100") (name "unconnected-(J87-Pad1)") (class "Default")
      (node (ref "J87") (pin "1") (pinfunction "1_1") (pintype "passive"))
    )
    (net (code "101") (name "unconnected-(J88-Pad1)") (class "Default")
      (node (ref "J88") (pin "1") (pinfunction "1_1") (pintype "passive"))
    )
    (net (code "102") (name "unconnected-(J90-Pad1)") (class "Default")
      (node (ref "J90") (pin "1") (pinfunction "1_1") (pintype "passive"))
    )
    (net (code "103") (name "unconnected-(U$2-CLK-Pad20)") (class "Default")
      (node (ref "U$2") (pin "20") (pinfunction "CLK_20") (pintype "bidirectional"))
    )
    (net (code "104") (name "unconnected-(U$2-CMD-Pad18)") (class "Default")
      (node (ref "U$2") (pin "18") (pinfunction "CMD_18") (pintype "bidirectional"))
    )
    (net (code "105") (name "unconnected-(U$2-EN-Pad2)") (class "Default")
      (node (ref "U$2") (pin "2") (pinfunction "EN_2") (pintype "bidirectional"))
    )
    (net (code "106") (name "unconnected-(U$2-IO0-Pad25)") (class "Default")
      (node (ref "U$2") (pin "25") (pinfunction "IO0_25") (pintype "bidirectional"))
    )
    (net (code "107") (name "unconnected-(U$2-IO2-Pad24)") (class "Default")
      (node (ref "U$2") (pin "24") (pinfunction "IO2_24") (pintype "bidirectional"))
    )
    (net (code "108") (name "unconnected-(U$2-IO4-Pad26)") (class "Default")
      (node (ref "U$2") (pin "26") (pinfunction "IO4_26") (pintype "bidirectional"))
    )
    (net (code "109") (name "unconnected-(U$2-IO5-Pad29)") (class "Default")
      (node (ref "U$2") (pin "29") (pinfunction "IO5_29") (pintype "bidirectional"))
    )
    (net (code "110") (name "unconnected-(U$2-IO12-Pad13)") (class "Default")
      (node (ref "U$2") (pin "13") (pinfunction "IO12_13") (pintype "bidirectional"))
    )
    (net (code "111") (name "unconnected-(U$2-RXD0-Pad34)") (class "Default")
      (node (ref "U$2") (pin "34") (pinfunction "RXD0_34") (pintype "bidirectional"))
    )
    (net (code "112") (name "unconnected-(U$2-SD0-Pad21)") (class "Default")
      (node (ref "U$2") (pin "21") (pinfunction "SD0_21") (pintype "bidirectional"))
    )
    (net (code "113") (name "unconnected-(U$2-SD1-Pad22)") (class "Default")
      (node (ref "U$2") (pin "22") (pinfunction "SD1_22") (pintype "bidirectional"))
    )
    (net (code "114") (name "unconnected-(U$2-SD2-Pad16)") (class "Default")
      (node (ref "U$2") (pin "16") (pinfunction "SD2_16") (pintype "bidirectional"))
    )
    (net (code "115") (name "unconnected-(U$2-SD3-Pad17)") (class "Default")
      (node (ref "U$2") (pin "17") (pinfunction "SD3_17") (pintype "bidirectional"))
    )
    (net (code "116") (name "unconnected-(U$2-SVN-Pad4)") (class "Default")
      (node (ref "U$2") (pin "4") (pinfunction "SVN_4") (pintype "bidirectional"))
    )
    (net (code "117") (name "unconnected-(U$2-SVP-Pad3)") (class "Default")
      (node (ref "U$2") (pin "3") (pinfunction "SVP_3") (pintype "bidirectional"))
    )
    (net (code "118") (name "unconnected-(U$2-TXD0-Pad35)") (class "Default")
      (node (ref "U$2") (pin "35") (pinfunction "TXD0_35") (pintype "bidirectional"))
    )
  )
)
